# Connectors.net
KiCad netlist of a schematic drawn in Altium Designer
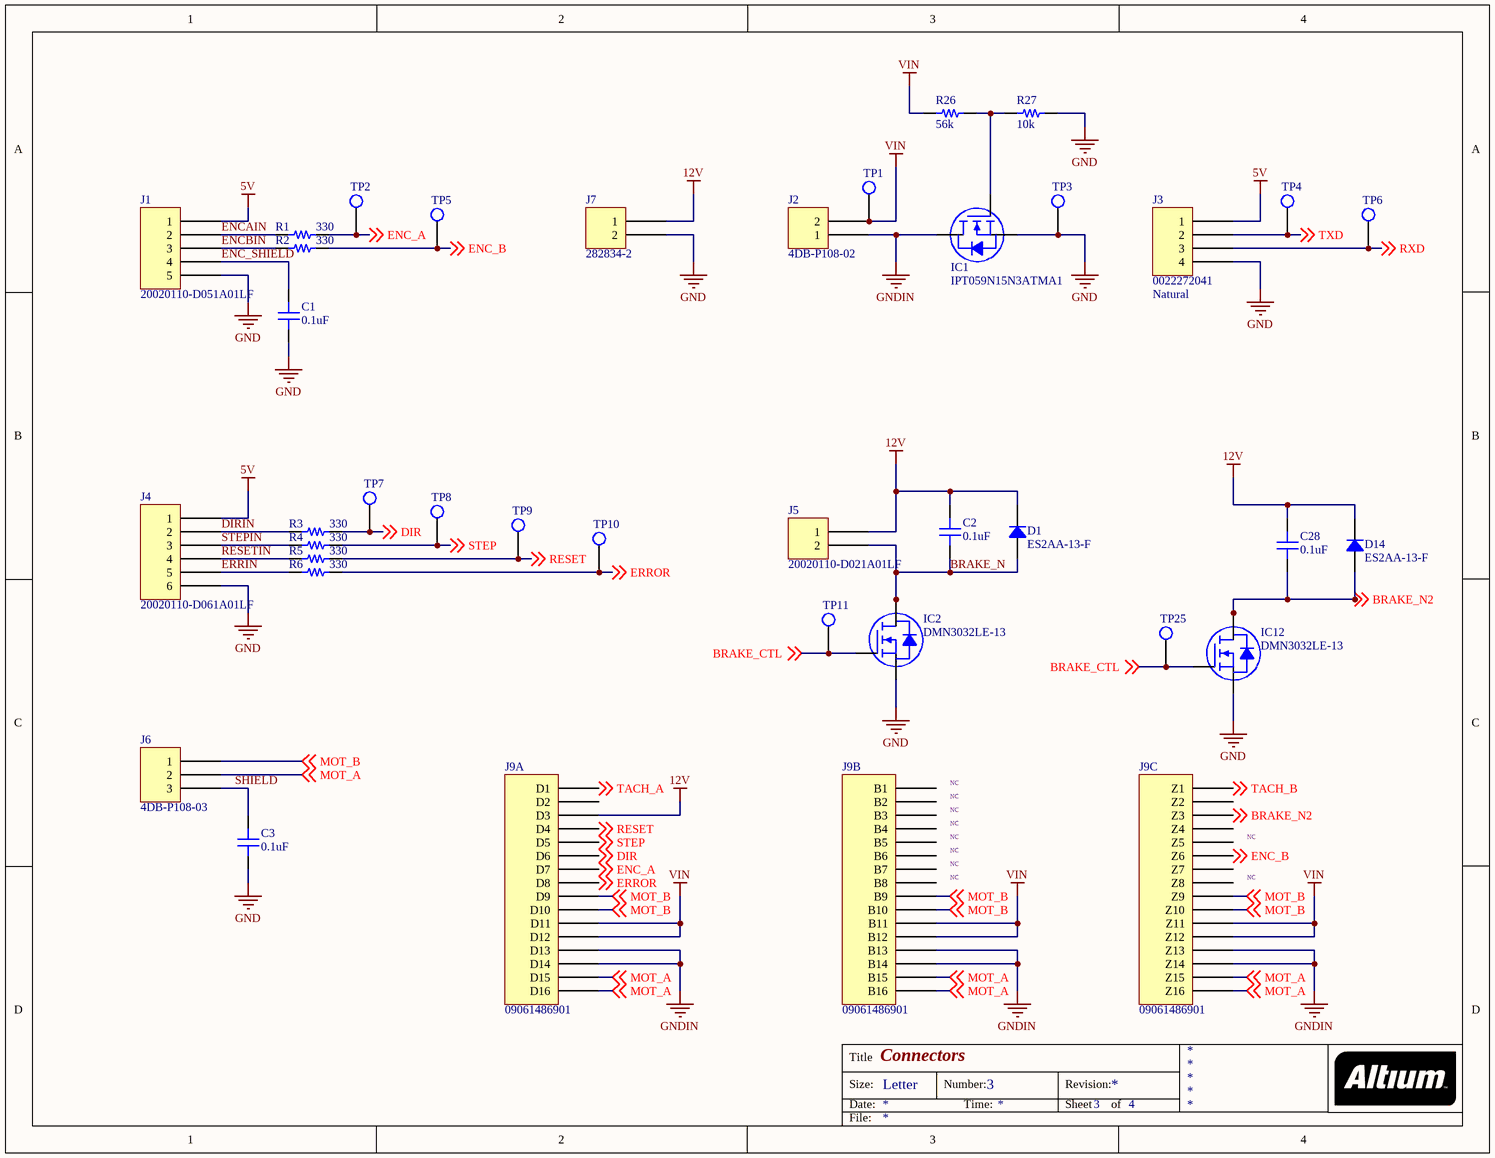
[diagram p0: Connectors.SchDoc]

(export (version "E")
  (design (tool "Eeschema 10.0.6"))
  (components
    (comp (ref "C1")
      (value "0.1uF")
      (footprint "CAP 0805/2012")
      (description "CAP CER 0.1UF 100V X5R 0805")
      (fields
        (field (name "PART NUMBER") "C2012X5R2A104K125AA")
        (field (name "MANUFACTURER") "TDK Corporation")
      )
      (libsource (lib "Celestial Library Database") (part "Capacitor"))
    )
    (comp (ref "C2")
      (value "0.1uF")
      (footprint "CAP 0805/2012")
      (description "CAP CER 0.1UF 100V X5R 0805")
      (fields
        (field (name "PART NUMBER") "C2012X5R2A104K125AA")
        (field (name "MANUFACTURER") "TDK Corporation")
      )
      (libsource (lib "Celestial Library Database") (part "Capacitor"))
    )
    (comp (ref "C3")
      (value "0.1uF")
      (footprint "CAP 0805/2012")
      (description "CAP CER 0.1UF 100V X5R 0805")
      (fields
        (field (name "PART NUMBER") "C2012X5R2A104K125AA")
        (field (name "MANUFACTURER") "TDK Corporation")
      )
      (libsource (lib "Celestial Library Database") (part "Capacitor"))
    )
    (comp (ref "C28")
      (value "0.1uF")
      (footprint "CAP 0805/2012")
      (description "CAP CER 0.1UF 100V X5R 0805")
      (fields
        (field (name "PART NUMBER") "C2012X5R2A104K125AA")
        (field (name "MANUFACTURER") "TDK Corporation")
      )
      (libsource (lib "Celestial Library Database") (part "Capacitor"))
    )
    (comp (ref "D1")
      (value "ES2AA-13-F")
      (footprint "DO214AC SMA")
      (description "DIODE GEN PURP 50V 2A SMA")
      (fields (field (name "MANUFACTURER") "Diodes Incorporated"))
      (libsource (lib "Celestial Library Database") (part "Diode"))
    )
    (comp (ref "D14")
      (value "ES2AA-13-F")
      (footprint "DO214AC SMA")
      (description "DIODE GEN PURP 50V 2A SMA")
      (fields (field (name "MANUFACTURER") "Diodes Incorporated"))
      (libsource (lib "Celestial Library Database") (part "Diode"))
    )
    (comp (ref "IC1")
      (value "IPT059N15N3ATMA1")
      (footprint "INFINEON PG-HSOF-8-1")
      (description "MOSFET N-CH 150V 155A 8HSOF")
      (fields (field (name "MANUFACTURER") "Infineon Technologies"))
      (libsource (lib "Celestial Library Database") (part "INFINEON MOSFET IPT059N15N3"))
    )
    (comp (ref "IC2")
      (value "DMN3032LE-13")
      (footprint "DIODES SOT-223")
      (description "MOSFET N-CH 30V 5.6A SOT223")
      (fields (field (name "MANUFACTURER") "Diodes Incorporated"))
      (libsource (lib "Celestial Library Database") (part "DIODES INC MOSFET N-CH SOT-223"))
    )
    (comp (ref "IC12")
      (value "DMN3032LE-13")
      (footprint "DIODES SOT-223")
      (description "MOSFET N-CH 30V 5.6A SOT223")
      (fields (field (name "MANUFACTURER") "Diodes Incorporated"))
      (libsource (lib "Celestial Library Database") (part "DIODES INC MOSFET N-CH SOT-223"))
    )
    (comp (ref "J1")
      (value "20020110-D051A01LF")
      (footprint "FCI 06-381-5PIN")
      (description "TERM BLOCK HDR 5POS R/A 3.81MM")
      (fields (field (name "MANUFACTURER") "FCI") (field (name "VOLTAGE") "300V"))
      (libsource (lib "Celestial Library Database") (part "5 Pin"))
    )
    (comp (ref "J2")
      (value "4DB-P108-02")
      (footprint "TE 4DB-P108-02")
      (description "CONN BARRIER STRIP 2CIRC 0.325\"")
      (fields (field (name "MANUFACTURER") "TE Connectivity AMP Connectors") (field (name "VOLTAGE") "150V"))
      (libsource (lib "") (part "2 Pin_1"))
    )
    (comp (ref "J3")
      (value "0022272041")
      (footprint "MOLEX KK 0022272041")
      (description "CONN HEADER 4POS .100 VERT TIN")
      (fields (field (name "COLOUR") "Natural") (field (name "MANUFACTURER") "Molex, LLC"))
      (libsource (lib "Celestial Library Database") (part "4 Pin"))
    )
    (comp (ref "J4")
      (value "20020110-D061A01LF")
      (footprint "FCI 06-381-6PIN")
      (description "TERM BLOCK HDR 6POS R/A 3.81MM")
      (fields (field (name "MANUFACTURER") "FCI") (field (name "VOLTAGE") "300V"))
      (libsource (lib "Celestial Library Database") (part "6 Pin"))
    )
    (comp (ref "J5")
      (value "20020110-D021A01LF")
      (footprint "FCI 06-381-2PIN")
      (description "TERM BLOCK HDR 2POS R/A 3.81MM")
      (fields (field (name "MANUFACTURER") "FCI") (field (name "VOLTAGE") "300V"))
      (libsource (lib "Celestial Library Database") (part "2 Pin"))
    )
    (comp (ref "J6")
      (value "4DB-P108-03")
      (footprint "TE 4DB-P108-03")
      (description "CONN BARRIER STRIP 3CIRC 0.325\"")
      (fields (field (name "MANUFACTURER") "TE Connectivity AMP Connectors") (field (name "VOLTAGE") "150V"))
      (libsource (lib "Celestial Library Database") (part "3 Pin"))
    )
    (comp (ref "J7")
      (value "282834-2")
      (footprint "TE 282834-2")
      (description "TERM BLOCK 2POS SIDE ENT 2.54MM")
      (fields (field (name "MANUFACTURER") "TE Connectivity AMP Connectors") (field (name "VOLTAGE") "150V"))
      (libsource (lib "Celestial Library Database") (part "2 Pin"))
    )
    (comp (ref "J9")
      (value "09061486901")
      (footprint "HARTING 09061486901")
      (description "DIN-POWER F048MS-3,0C1-2")
      (fields (field (name "MANUFACTURER") "Harting"))
      (libsource (lib "Celestial Library Database") (part "DIN 41612 48Pos 3Row"))
    )
    (comp (ref "R1")
      (value "330")
      (footprint "RES 0603/1608")
      (description "RES SMD 330 OHM 5% 1/10W 0603")
      (fields
        (field (name "PART NUMBER") "ERJ-3GEYJ331V")
        (field (name "MANUFACTURER") "Panasonic Electronic Components")
      )
      (libsource (lib "Celestial Library Database") (part "Resistor"))
    )
    (comp (ref "R2")
      (value "330")
      (footprint "RES 0603/1608")
      (description "RES SMD 330 OHM 5% 1/10W 0603")
      (fields
        (field (name "PART NUMBER") "ERJ-3GEYJ331V")
        (field (name "MANUFACTURER") "Panasonic Electronic Components")
      )
      (libsource (lib "Celestial Library Database") (part "Resistor"))
    )
    (comp (ref "R3")
      (value "330")
      (footprint "RES 0603/1608")
      (description "RES SMD 330 OHM 5% 1/10W 0603")
      (fields
        (field (name "PART NUMBER") "ERJ-3GEYJ331V")
        (field (name "MANUFACTURER") "Panasonic Electronic Components")
      )
      (libsource (lib "Celestial Library Database") (part "Resistor"))
    )
    (comp (ref "R4")
      (value "330")
      (footprint "RES 0603/1608")
      (description "RES SMD 330 OHM 5% 1/10W 0603")
      (fields
        (field (name "PART NUMBER") "ERJ-3GEYJ331V")
        (field (name "MANUFACTURER") "Panasonic Electronic Components")
      )
      (libsource (lib "Celestial Library Database") (part "Resistor"))
    )
    (comp (ref "R5")
      (value "330")
      (footprint "RES 0603/1608")
      (description "RES SMD 330 OHM 5% 1/10W 0603")
      (fields
        (field (name "PART NUMBER") "ERJ-3GEYJ331V")
        (field (name "MANUFACTURER") "Panasonic Electronic Components")
      )
      (libsource (lib "Celestial Library Database") (part "Resistor"))
    )
    (comp (ref "R6")
      (value "330")
      (footprint "RES 0603/1608")
      (description "RES SMD 330 OHM 5% 1/10W 0603")
      (fields
        (field (name "PART NUMBER") "ERJ-3GEYJ331V")
        (field (name "MANUFACTURER") "Panasonic Electronic Components")
      )
      (libsource (lib "Celestial Library Database") (part "Resistor"))
    )
    (comp (ref "R26")
      (value "56k")
      (footprint "RES 0603/1608")
      (description "RES SMD 56K OHM 1% 1/10W 0603")
      (fields
        (field (name "PART NUMBER") "ERJ-3EKF5602V")
        (field (name "MANUFACTURER") "Panasonic Electronic Components")
      )
      (libsource (lib "Celestial Library Database") (part "Resistor"))
    )
    (comp (ref "R27")
      (value "10k")
      (footprint "RES 0603/1608")
      (description "RES SMD 10K OHM 1% 1/10W 0603")
      (fields
        (field (name "PART NUMBER") "ERJ-3EKF1002V")
        (field (name "MANUFACTURER") "Panasonic Electronic Components")
      )
      (libsource (lib "Celestial Library Database") (part "Resistor"))
    )
    (comp (ref "TP1")
      (value "Test Point")
      (footprint "Test Point")
      (libsource (lib "Motor Controller") (part "Test Point"))
    )
    (comp (ref "TP2")
      (value "Test Point")
      (footprint "Test Point")
      (libsource (lib "Motor Controller") (part "Test Point"))
    )
    (comp (ref "TP3")
      (value "Test Point")
      (footprint "Test Point")
      (libsource (lib "Motor Controller") (part "Test Point"))
    )
    (comp (ref "TP4")
      (value "Test Point")
      (footprint "Test Point")
      (libsource (lib "Motor Controller") (part "Test Point"))
    )
    (comp (ref "TP5")
      (value "Test Point")
      (footprint "Test Point")
      (libsource (lib "Motor Controller") (part "Test Point"))
    )
    (comp (ref "TP6")
      (value "Test Point")
      (footprint "Test Point")
      (libsource (lib "Motor Controller") (part "Test Point"))
    )
    (comp (ref "TP7")
      (value "Test Point")
      (footprint "Test Point")
      (libsource (lib "Motor Controller") (part "Test Point"))
    )
    (comp (ref "TP8")
      (value "Test Point")
      (footprint "Test Point")
      (libsource (lib "Motor Controller") (part "Test Point"))
    )
    (comp (ref "TP9")
      (value "Test Point")
      (footprint "Test Point")
      (libsource (lib "Motor Controller") (part "Test Point"))
    )
    (comp (ref "TP10")
      (value "Test Point")
      (footprint "Test Point")
      (libsource (lib "Motor Controller") (part "Test Point"))
    )
    (comp (ref "TP11")
      (value "Test Point")
      (footprint "Test Point")
      (libsource (lib "Motor Controller") (part "Test Point"))
    )
    (comp (ref "TP25")
      (value "Test Point")
      (footprint "Test Point")
      (libsource (lib "Motor Controller") (part "Test Point"))
    )
  )
  (nets
    (net (code "1") (name "/BRAKE_N") (class "Default")
      (node (ref "C2") (pin "1") (pinfunction "1_1") (pintype "passive"))
      (node (ref "D1") (pin "1") (pinfunction "1_1") (pintype "passive"))
      (node (ref "IC2") (pin "2") (pinfunction "D_2") (pintype "passive"))
      (node (ref "IC2") (pin "4") (pinfunction "D_4") (pintype "passive"))
      (node (ref "J5") (pin "2") (pinfunction "2_2") (pintype "passive"))
    )
    (net (code "2") (name "/DIRIN") (class "Default")
      (node (ref "J4") (pin "2") (pinfunction "2_2") (pintype "passive"))
      (node (ref "R3") (pin "1") (pinfunction "1_1") (pintype "passive"))
    )
    (net (code "3") (name "/ENCAIN") (class "Default")
      (node (ref "J1") (pin "2") (pinfunction "2_2") (pintype "passive"))
      (node (ref "R1") (pin "1") (pinfunction "1_1") (pintype "passive"))
    )
    (net (code "4") (name "/ENCBIN") (class "Default")
      (node (ref "J1") (pin "3") (pinfunction "3_3") (pintype "passive"))
      (node (ref "R2") (pin "1") (pinfunction "1_1") (pintype "passive"))
    )
    (net (code "5") (name "/ENC_SHIELD") (class "Default")
      (node (ref "C1") (pin "2") (pinfunction "2_2") (pintype "passive"))
      (node (ref "J1") (pin "4") (pinfunction "4_4") (pintype "passive"))
    )
    (net (code "6") (name "/ERRIN") (class "Default")
      (node (ref "J4") (pin "5") (pinfunction "5_5") (pintype "passive"))
      (node (ref "R6") (pin "1") (pinfunction "1_1") (pintype "passive"))
    )
    (net (code "7") (name "/RESETIN") (class "Default")
      (node (ref "J4") (pin "4") (pinfunction "4_4") (pintype "passive"))
      (node (ref "R5") (pin "1") (pinfunction "1_1") (pintype "passive"))
    )
    (net (code "8") (name "/SHIELD") (class "Default")
      (node (ref "C3") (pin "2") (pinfunction "2_2") (pintype "passive"))
      (node (ref "J6") (pin "3") (pinfunction "3_3") (pintype "passive"))
    )
    (net (code "9") (name "/STEPIN") (class "Default")
      (node (ref "J4") (pin "3") (pinfunction "3_3") (pintype "passive"))
      (node (ref "R4") (pin "1") (pinfunction "1_1") (pintype "passive"))
    )
    (net (code "10") (name "5V") (class "Default")
      (node (ref "J1") (pin "1") (pinfunction "1_1") (pintype "passive"))
      (node (ref "J3") (pin "1") (pinfunction "1_1") (pintype "passive"))
      (node (ref "J4") (pin "1") (pinfunction "1_1") (pintype "passive"))
    )
    (net (code "11") (name "12V") (class "Default")
      (node (ref "C2") (pin "2") (pinfunction "2_2") (pintype "passive"))
      (node (ref "C28") (pin "2") (pinfunction "2_2") (pintype "passive"))
      (node (ref "D1") (pin "2") (pinfunction "2_2") (pintype "passive"))
      (node (ref "D14") (pin "2") (pinfunction "2_2") (pintype "passive"))
      (node (ref "J5") (pin "1") (pinfunction "1_1") (pintype "passive"))
      (node (ref "J7") (pin "1") (pinfunction "1_1") (pintype "passive"))
      (node (ref "J9") (pin "D3") (pinfunction "D3_D3") (pintype "passive"))
    )
    (net (code "12") (name "BRAKE_CTL") (class "Default")
      (node (ref "IC12") (pin "1") (pinfunction "G_1") (pintype "passive"))
      (node (ref "IC2") (pin "1") (pinfunction "G_1") (pintype "passive"))
      (node (ref "TP11") (pin "1") (pinfunction "TP_1") (pintype "passive"))
      (node (ref "TP25") (pin "1") (pinfunction "TP_1") (pintype "passive"))
    )
    (net (code "13") (name "BRAKE_N2") (class "Default")
      (node (ref "C28") (pin "1") (pinfunction "1_1") (pintype "passive"))
      (node (ref "D14") (pin "1") (pinfunction "1_1") (pintype "passive"))
      (node (ref "IC12") (pin "2") (pinfunction "D_2") (pintype "passive"))
      (node (ref "IC12") (pin "4") (pinfunction "D_4") (pintype "passive"))
      (node (ref "J9") (pin "Z3") (pinfunction "Z3_Z3") (pintype "passive"))
    )
    (net (code "14") (name "DIR") (class "Default")
      (node (ref "J9") (pin "D6") (pinfunction "D6_D6") (pintype "passive"))
      (node (ref "R3") (pin "2") (pinfunction "2_2") (pintype "passive"))
      (node (ref "TP7") (pin "1") (pinfunction "TP_1") (pintype "passive"))
    )
    (net (code "15") (name "ENC_A") (class "Default")
      (node (ref "J9") (pin "D7") (pinfunction "D7_D7") (pintype "passive"))
      (node (ref "R1") (pin "2") (pinfunction "2_2") (pintype "passive"))
      (node (ref "TP2") (pin "1") (pinfunction "TP_1") (pintype "passive"))
    )
    (net (code "16") (name "ENC_B") (class "Default")
      (node (ref "J9") (pin "Z6") (pinfunction "Z6_Z6") (pintype "passive"))
      (node (ref "R2") (pin "2") (pinfunction "2_2") (pintype "passive"))
      (node (ref "TP5") (pin "1") (pinfunction "TP_1") (pintype "passive"))
    )
    (net (code "17") (name "ERROR") (class "Default")
      (node (ref "J9") (pin "D8") (pinfunction "D8_D8") (pintype "passive"))
      (node (ref "R6") (pin "2") (pinfunction "2_2") (pintype "passive"))
      (node (ref "TP10") (pin "1") (pinfunction "TP_1") (pintype "passive"))
    )
    (net (code "18") (name "GND") (class "Default")
      (node (ref "C1") (pin "1") (pinfunction "1_1") (pintype "passive"))
      (node (ref "C3") (pin "1") (pinfunction "1_1") (pintype "passive"))
      (node (ref "IC1") (pin "S") (pinfunction "S_S") (pintype "passive"))
      (node (ref "IC12") (pin "3") (pinfunction "S_3") (pintype "passive"))
      (node (ref "IC2") (pin "3") (pinfunction "S_3") (pintype "passive"))
      (node (ref "J1") (pin "5") (pinfunction "5_5") (pintype "passive"))
      (node (ref "J3") (pin "4") (pinfunction "4_4") (pintype "passive"))
      (node (ref "J4") (pin "6") (pinfunction "6_6") (pintype "passive"))
      (node (ref "J7") (pin "2") (pinfunction "2_2") (pintype "passive"))
      (node (ref "R27") (pin "2") (pinfunction "2_2") (pintype "passive"))
      (node (ref "TP3") (pin "1") (pinfunction "TP_1") (pintype "passive"))
    )
    (net (code "19") (name "GNDIN") (class "Default")
      (node (ref "IC1") (pin "D") (pinfunction "D_D") (pintype "passive"))
      (node (ref "J2") (pin "1") (pinfunction "1_1") (pintype "passive"))
      (node (ref "J9") (pin "B13") (pinfunction "B13_B13") (pintype "passive"))
      (node (ref "J9") (pin "B14") (pinfunction "B14_B14") (pintype "passive"))
      (node (ref "J9") (pin "D13") (pinfunction "D13_D13") (pintype "passive"))
      (node (ref "J9") (pin "D14") (pinfunction "D14_D14") (pintype "passive"))
      (node (ref "J9") (pin "Z13") (pinfunction "Z13_Z13") (pintype "passive"))
      (node (ref "J9") (pin "Z14") (pinfunction "Z14_Z14") (pintype "passive"))
    )
    (net (code "20") (name "MOT_A") (class "Default")
      (node (ref "J6") (pin "2") (pinfunction "2_2") (pintype "passive"))
      (node (ref "J9") (pin "B15") (pinfunction "B15_B15") (pintype "passive"))
      (node (ref "J9") (pin "B16") (pinfunction "B16_B16") (pintype "passive"))
      (node (ref "J9") (pin "D15") (pinfunction "D15_D15") (pintype "passive"))
      (node (ref "J9") (pin "D16") (pinfunction "D16_D16") (pintype "passive"))
      (node (ref "J9") (pin "Z15") (pinfunction "Z15_Z15") (pintype "passive"))
      (node (ref "J9") (pin "Z16") (pinfunction "Z16_Z16") (pintype "passive"))
    )
    (net (code "21") (name "MOT_B") (class "Default")
      (node (ref "J6") (pin "1") (pinfunction "1_1") (pintype "passive"))
      (node (ref "J9") (pin "B10") (pinfunction "B10_B10") (pintype "passive"))
      (node (ref "J9") (pin "B9") (pinfunction "B9_B9") (pintype "passive"))
      (node (ref "J9") (pin "D10") (pinfunction "D10_D10") (pintype "passive"))
      (node (ref "J9") (pin "D9") (pinfunction "D9_D9") (pintype "passive"))
      (node (ref "J9") (pin "Z10") (pinfunction "Z10_Z10") (pintype "passive"))
      (node (ref "J9") (pin "Z9") (pinfunction "Z9_Z9") (pintype "passive"))
    )
    (net (code "22") (name "Net-(IC1-PadG)") (class "Default")
      (node (ref "IC1") (pin "G") (pinfunction "G_G") (pintype "passive"))
      (node (ref "R26") (pin "2") (pinfunction "2_2") (pintype "passive"))
      (node (ref "R27") (pin "1") (pinfunction "1_1") (pintype "passive"))
    )
    (net (code "23") (name "RESET") (class "Default")
      (node (ref "J9") (pin "D4") (pinfunction "D4_D4") (pintype "passive"))
      (node (ref "R5") (pin "2") (pinfunction "2_2") (pintype "passive"))
      (node (ref "TP9") (pin "1") (pinfunction "TP_1") (pintype "passive"))
    )
    (net (code "24") (name "RXD") (class "Default")
      (node (ref "J3") (pin "3") (pinfunction "3_3") (pintype "passive"))
      (node (ref "TP6") (pin "1") (pinfunction "TP_1") (pintype "passive"))
    )
    (net (code "25") (name "STEP") (class "Default")
      (node (ref "J9") (pin "D5") (pinfunction "D5_D5") (pintype "passive"))
      (node (ref "R4") (pin "2") (pinfunction "2_2") (pintype "passive"))
      (node (ref "TP8") (pin "1") (pinfunction "TP_1") (pintype "passive"))
    )
    (net (code "26") (name "TACH_A") (class "Default")
      (node (ref "J9") (pin "D1") (pinfunction "D1_D1") (pintype "passive"))
    )
    (net (code "27") (name "TACH_B") (class "Default")
      (node (ref "J9") (pin "Z1") (pinfunction "Z1_Z1") (pintype "passive"))
    )
    (net (code "28") (name "TXD") (class "Default")
      (node (ref "J3") (pin "2") (pinfunction "2_2") (pintype "passive"))
      (node (ref "TP4") (pin "1") (pinfunction "TP_1") (pintype "passive"))
    )
    (net (code "29") (name "VIN") (class "Default")
      (node (ref "J2") (pin "2") (pinfunction "2_2") (pintype "passive"))
      (node (ref "J9") (pin "B11") (pinfunction "B11_B11") (pintype "passive"))
      (node (ref "J9") (pin "B12") (pinfunction "B12_B12") (pintype "passive"))
      (node (ref "J9") (pin "D11") (pinfunction "D11_D11") (pintype "passive"))
      (node (ref "J9") (pin "D12") (pinfunction "D12_D12") (pintype "passive"))
      (node (ref "J9") (pin "Z11") (pinfunction "Z11_Z11") (pintype "passive"))
      (node (ref "J9") (pin "Z12") (pinfunction "Z12_Z12") (pintype "passive"))
      (node (ref "R26") (pin "1") (pinfunction "1_1") (pintype "passive"))
      (node (ref "TP1") (pin "1") (pinfunction "TP_1") (pintype "passive"))
    )
    (net (code "30") (name "unconnected-(J9-PadB1)") (class "Default")
      (node (ref "J9") (pin "B1") (pinfunction "B1_B1") (pintype "passive"))
    )
    (net (code "31") (name "unconnected-(J9-PadB2)") (class "Default")
      (node (ref "J9") (pin "B2") (pinfunction "B2_B2") (pintype "passive"))
    )
    (net (code "32") (name "unconnected-(J9-PadB3)") (class "Default")
      (node (ref "J9") (pin "B3") (pinfunction "B3_B3") (pintype "passive"))
    )
    (net (code "33") (name "unconnected-(J9-PadB4)") (class "Default")
      (node (ref "J9") (pin "B4") (pinfunction "B4_B4") (pintype "passive"))
    )
    (net (code "34") (name "unconnected-(J9-PadB5)") (class "Default")
      (node (ref "J9") (pin "B5") (pinfunction "B5_B5") (pintype "passive"))
    )
    (net (code "35") (name "unconnected-(J9-PadB6)") (class "Default")
      (node (ref "J9") (pin "B6") (pinfunction "B6_B6") (pintype "passive"))
    )
    (net (code "36") (name "unconnected-(J9-PadB7)") (class "Default")
      (node (ref "J9") (pin "B7") (pinfunction "B7_B7") (pintype "passive"))
    )
    (net (code "37") (name "unconnected-(J9-PadB8)") (class "Default")
      (node (ref "J9") (pin "B8") (pinfunction "B8_B8") (pintype "passive"))
    )
    (net (code "38") (name "unconnected-(J9-PadD2)") (class "Default")
      (node (ref "J9") (pin "D2") (pinfunction "D2_D2") (pintype "passive"))
    )
    (net (code "39") (name "unconnected-(J9-PadZ2)") (class "Default")
      (node (ref "J9") (pin "Z2") (pinfunction "Z2_Z2") (pintype "passive"))
    )
    (net (code "40") (name "unconnected-(J9-PadZ4)") (class "Default")
      (node (ref "J9") (pin "Z4") (pinfunction "Z4_Z4") (pintype "passive"))
    )
    (net (code "41") (name "unconnected-(J9-PadZ5)") (class "Default")
      (node (ref "J9") (pin "Z5") (pinfunction "Z5_Z5") (pintype "passive"))
    )
    (net (code "42") (name "unconnected-(J9-PadZ7)") (class "Default")
      (node (ref "J9") (pin "Z7") (pinfunction "Z7_Z7") (pintype "passive"))
    )
    (net (code "43") (name "unconnected-(J9-PadZ8)") (class "Default")
      (node (ref "J9") (pin "Z8") (pinfunction "Z8_Z8") (pintype "passive"))
    )
  )
)
